# Connector.net
KiCad netlist of a schematic drawn in Altium Designer
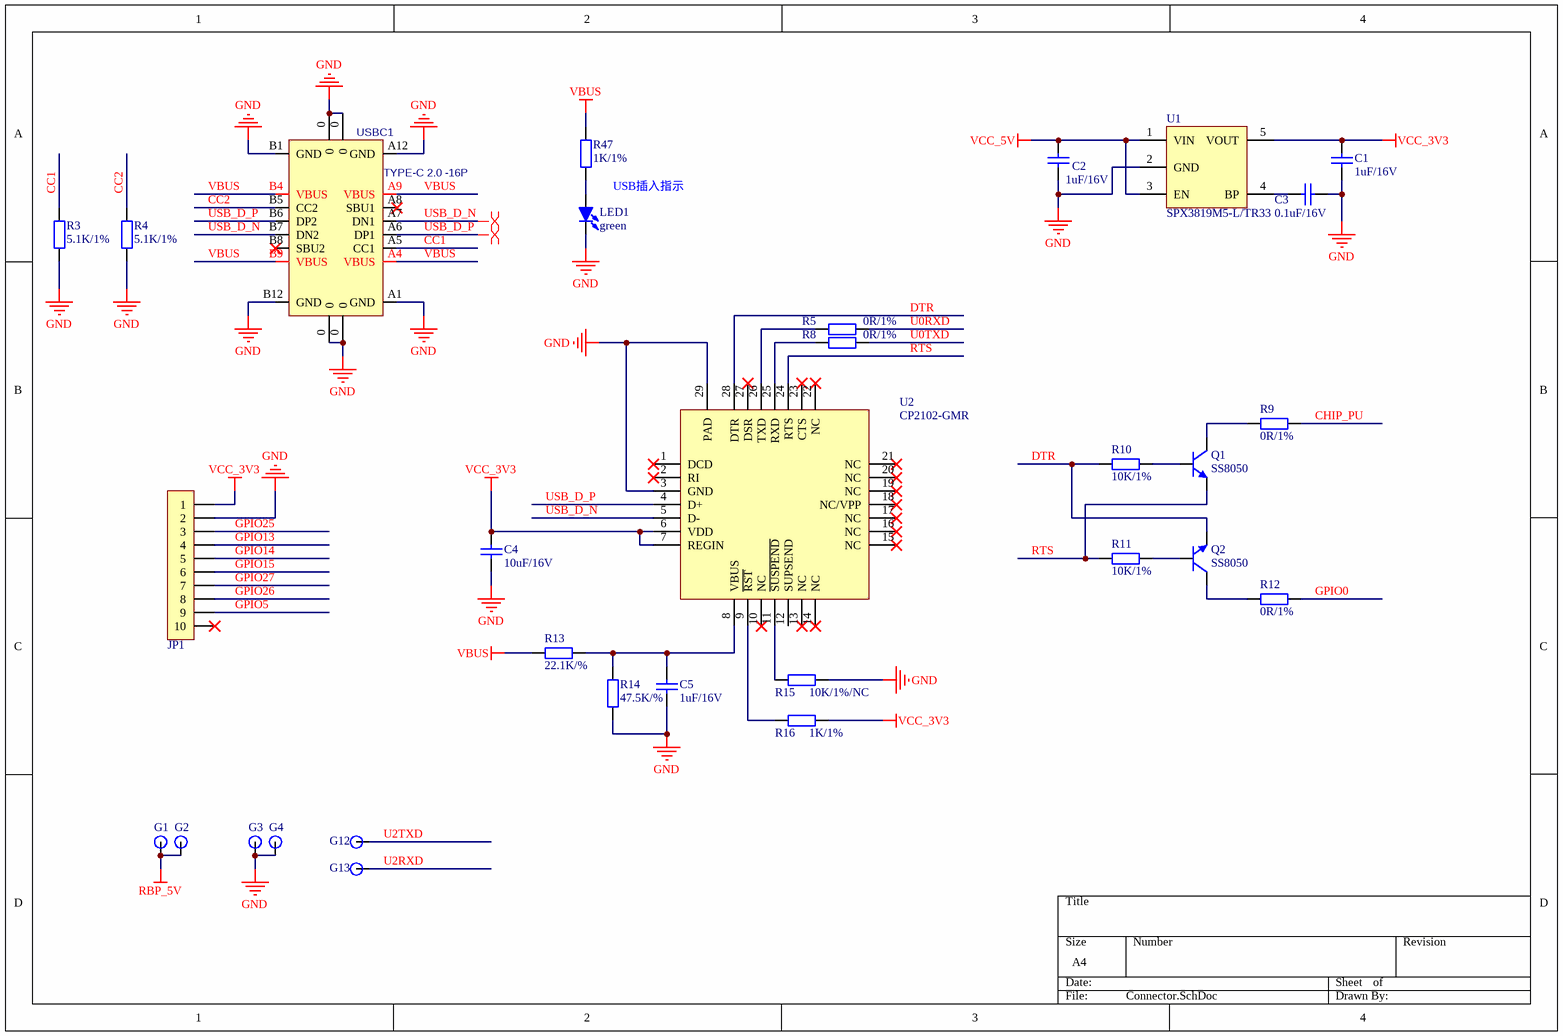
[diagram p0: Connector.SchDoc]

(export (version "E")
  (design (tool "Eeschema 10.0.6"))
  (components
    (comp (ref "C1")
      (value "1uF/16V")
      (footprint "C0402_L")
      (description "贴片电容")
      (libsource (lib "0.1 - 电阻-电容-电感-晶振-晶体-磁珠-电位器") (part "C"))
    )
    (comp (ref "C2")
      (value "1uF/16V")
      (footprint "C0402_L")
      (description "贴片电容")
      (libsource (lib "0.1 - 电阻-电容-电感-晶振-晶体-磁珠-电位器") (part "C"))
    )
    (comp (ref "C3")
      (value "0.1uF/16V")
      (footprint "C0402_L")
      (description "贴片电容")
      (libsource (lib "0.1 - 电阻-电容-电感-晶振-晶体-磁珠-电位器") (part "C"))
    )
    (comp (ref "C4")
      (value "10uF/16V")
      (footprint "C0603_L")
      (description "贴片电容")
      (libsource (lib "0.1 - 电阻-电容-电感-晶振-晶体-磁珠-电位器") (part "C"))
    )
    (comp (ref "C5")
      (value "1uF/16V")
      (footprint "C0402_L")
      (description "贴片电容")
      (libsource (lib "0.1 - 电阻-电容-电感-晶振-晶体-磁珠-电位器") (part "C"))
    )
    (comp (ref "G1") (value "RBP_GPIO") (footprint "PA100-A3") (libsource (lib "USER_Lib") (part "RBP_GPIO")))
    (comp (ref "G2") (value "RBP_GPIO") (footprint "PA100-A3") (libsource (lib "USER_Lib") (part "RBP_GPIO")))
    (comp (ref "G3") (value "RBP_GPIO") (footprint "PA100-A3") (libsource (lib "USER_Lib") (part "RBP_GPIO")))
    (comp (ref "G4") (value "RBP_GPIO") (footprint "PA100-A3") (libsource (lib "USER_Lib") (part "RBP_GPIO")))
    (comp (ref "G12")
      (value "RBP_GPIO")
      (footprint "PA100-A3")
      (libsource (lib "USER_Lib") (part "RBP_GPIO"))
    )
    (comp (ref "G13")
      (value "RBP_GPIO")
      (footprint "PA100-A3")
      (libsource (lib "USER_Lib") (part "RBP_GPIO"))
    )
    (comp (ref "JP1")
      (value "CON-10P")
      (footprint "SH1.0-WT-10P")
      (description "10P连接器")
      (libsource (lib "5.0 - 1.00mm连接器(FPC1.0-SH1.0)") (part "Header 10"))
    )
    (comp (ref "LED1")
      (value "green")
      (footprint "LED0402")
      (description "贴片LED")
      (libsource (lib "0.3 - LED发光二极管-IR二极管_接收管-光耦") (part "LED-SMD"))
    )
    (comp (ref "Q1")
      (value "SS8050")
      (footprint "SOT23-3L")
      (description "高频放大-NPN型")
      (libsource (lib "0.4 - 三极管-场效应管-可控硅") (part "8050-SMD"))
    )
    (comp (ref "Q2")
      (value "SS8050")
      (footprint "SOT23-3L")
      (description "高频放大-NPN型")
      (libsource (lib "0.4 - 三极管-场效应管-可控硅") (part "8050-SMD"))
    )
    (comp (ref "R3")
      (value "5.1K/1%")
      (footprint "R0402_L")
      (description "贴片电阻")
      (libsource (lib "0.1 - 电阻-电容-电感-晶振-晶体-磁珠-电位器") (part "R"))
    )
    (comp (ref "R4")
      (value "5.1K/1%")
      (footprint "R0402_L")
      (description "贴片电阻")
      (libsource (lib "0.1 - 电阻-电容-电感-晶振-晶体-磁珠-电位器") (part "R"))
    )
    (comp (ref "R5")
      (value "0R/1%")
      (footprint "R0402_L")
      (description "贴片电阻")
      (libsource (lib "0.1 - 电阻-电容-电感-晶振-晶体-磁珠-电位器") (part "R"))
    )
    (comp (ref "R8")
      (value "0R/1%")
      (footprint "R0402_L")
      (description "贴片电阻")
      (libsource (lib "0.1 - 电阻-电容-电感-晶振-晶体-磁珠-电位器") (part "R"))
    )
    (comp (ref "R9")
      (value "0R/1%")
      (footprint "R0402_L")
      (description "贴片电阻")
      (libsource (lib "0.1 - 电阻-电容-电感-晶振-晶体-磁珠-电位器") (part "R"))
    )
    (comp (ref "R10")
      (value "10K/1%")
      (footprint "R0402_L")
      (description "贴片电阻")
      (libsource (lib "0.1 - 电阻-电容-电感-晶振-晶体-磁珠-电位器") (part "R"))
    )
    (comp (ref "R11")
      (value "10K/1%")
      (footprint "R0402_L")
      (description "贴片电阻")
      (libsource (lib "0.1 - 电阻-电容-电感-晶振-晶体-磁珠-电位器") (part "R"))
    )
    (comp (ref "R12")
      (value "0R/1%")
      (footprint "R0402_L")
      (description "贴片电阻")
      (libsource (lib "0.1 - 电阻-电容-电感-晶振-晶体-磁珠-电位器") (part "R"))
    )
    (comp (ref "R13")
      (value "22.1K/%")
      (footprint "R0402_L")
      (description "贴片电阻")
      (libsource (lib "0.1 - 电阻-电容-电感-晶振-晶体-磁珠-电位器") (part "R"))
    )
    (comp (ref "R14")
      (value "47.5K/%")
      (footprint "R0402_L")
      (description "贴片电阻")
      (libsource (lib "0.1 - 电阻-电容-电感-晶振-晶体-磁珠-电位器") (part "R"))
    )
    (comp (ref "R15")
      (value "10K/1%/NC")
      (footprint "R0402_L")
      (description "贴片电阻")
      (libsource (lib "0.1 - 电阻-电容-电感-晶振-晶体-磁珠-电位器") (part "R"))
    )
    (comp (ref "R16")
      (value "1K/1%")
      (footprint "R0402_L")
      (description "贴片电阻")
      (libsource (lib "0.1 - 电阻-电容-电感-晶振-晶体-磁珠-电位器") (part "R"))
    )
    (comp (ref "R47")
      (value "1K/1%")
      (footprint "R0402_L")
      (description "贴片电阻")
      (libsource (lib "0.1 - 电阻-电容-电感-晶振-晶体-磁珠-电位器") (part "R"))
    )
    (comp (ref "U1")
      (value "SPX3819M5-L/TR33")
      (footprint "SOT23-5L")
      (description "500ma-LDO")
      (libsource (lib "USER_Lib") (part "SPX3819M5"))
    )
    (comp (ref "U2")
      (value "CP2102-GMR")
      (footprint "QFN28 5x5_L")
      (description "USB-TTL")
      (libsource (lib "USER_Lib") (part "CP2102-GMR"))
    )
    (comp (ref "USBC1")
      (value "TYPE-C 2.0 -16P")
      (footprint "USB-C-SMD_16P")
      (description "USB2.0_Type-C_16Pin母座")
      (libsource (lib "0.6 - 电源-以太网-音频-Type-C USB插座") (part "USB2.0_Type-C_16Pin"))
    )
  )
  (nets
    (net (code "1") (name "/CC1") (class "Default")
      (node (ref "R3") (pin "2") (pinfunction "2_2") (pintype "passive"))
      (node (ref "USBC1") (pin "A5") (pinfunction "CC1_A5") (pintype "passive"))
    )
    (net (code "2") (name "/CC2") (class "Default")
      (node (ref "R4") (pin "2") (pinfunction "2_2") (pintype "passive"))
      (node (ref "USBC1") (pin "B5") (pinfunction "CC2_B5") (pintype "passive"))
    )
    (net (code "3") (name "/CHIP_PU") (class "Default")
      (node (ref "R9") (pin "2") (pinfunction "2_2") (pintype "passive"))
    )
    (net (code "4") (name "/DTR") (class "Default")
      (node (ref "Q2") (pin "2") (pinfunction "E_2") (pintype "passive"))
      (node (ref "R10") (pin "1") (pinfunction "1_1") (pintype "passive"))
      (node (ref "U2") (pin "28") (pinfunction "DTR_28") (pintype "passive"))
    )
    (net (code "5") (name "/GPIO0") (class "Default")
      (node (ref "R12") (pin "2") (pinfunction "2_2") (pintype "passive"))
    )
    (net (code "6") (name "/GPIO5") (class "Default")
      (node (ref "JP1") (pin "9") (pinfunction "9_9") (pintype "passive"))
    )
    (net (code "7") (name "/GPIO13") (class "Default")
      (node (ref "JP1") (pin "4") (pinfunction "4_4") (pintype "passive"))
    )
    (net (code "8") (name "/GPIO14") (class "Default")
      (node (ref "JP1") (pin "5") (pinfunction "5_5") (pintype "passive"))
    )
    (net (code "9") (name "/GPIO15") (class "Default")
      (node (ref "JP1") (pin "6") (pinfunction "6_6") (pintype "passive"))
    )
    (net (code "10") (name "/GPIO25") (class "Default")
      (node (ref "JP1") (pin "3") (pinfunction "3_3") (pintype "passive"))
    )
    (net (code "11") (name "/GPIO26") (class "Default")
      (node (ref "JP1") (pin "8") (pinfunction "8_8") (pintype "passive"))
    )
    (net (code "12") (name "/GPIO27") (class "Default")
      (node (ref "JP1") (pin "7") (pinfunction "7_7") (pintype "passive"))
    )
    (net (code "13") (name "/RTS") (class "Default")
      (node (ref "Q1") (pin "2") (pinfunction "E_2") (pintype "passive"))
      (node (ref "R11") (pin "1") (pinfunction "1_1") (pintype "passive"))
      (node (ref "U2") (pin "24") (pinfunction "RTS_24") (pintype "passive"))
    )
    (net (code "14") (name "/U0RXD") (class "Default")
      (node (ref "R5") (pin "2") (pinfunction "2_2") (pintype "passive"))
    )
    (net (code "15") (name "/U0TXD") (class "Default")
      (node (ref "R8") (pin "2") (pinfunction "2_2") (pintype "passive"))
    )
    (net (code "16") (name "/U2RXD") (class "Default")
      (node (ref "G13") (pin "1") (pinfunction "1_1") (pintype "passive"))
    )
    (net (code "17") (name "/U2TXD") (class "Default")
      (node (ref "G12") (pin "1") (pinfunction "1_1") (pintype "passive"))
    )
    (net (code "18") (name "/USB_D_N") (class "Default")
      (node (ref "U2") (pin "5") (pinfunction "D-_5") (pintype "passive"))
      (node (ref "USBC1") (pin "A7") (pinfunction "DN1_A7") (pintype "passive"))
      (node (ref "USBC1") (pin "B7") (pinfunction "DN2_B7") (pintype "passive"))
    )
    (net (code "19") (name "/USB_D_P") (class "Default")
      (node (ref "U2") (pin "4") (pinfunction "D+_4") (pintype "passive"))
      (node (ref "USBC1") (pin "A6") (pinfunction "DP1_A6") (pintype "passive"))
      (node (ref "USBC1") (pin "B6") (pinfunction "DP2_B6") (pintype "passive"))
    )
    (net (code "20") (name "GND") (class "Default")
      (node (ref "C1") (pin "2") (pinfunction "2_2") (pintype "passive"))
      (node (ref "C2") (pin "1") (pinfunction "1_1") (pintype "passive"))
      (node (ref "C3") (pin "2") (pinfunction "2_2") (pintype "passive"))
      (node (ref "C4") (pin "1") (pinfunction "1_1") (pintype "passive"))
      (node (ref "C5") (pin "1") (pinfunction "1_1") (pintype "passive"))
      (node (ref "G3") (pin "1") (pinfunction "1_1") (pintype "passive"))
      (node (ref "G4") (pin "1") (pinfunction "1_1") (pintype "passive"))
      (node (ref "JP1") (pin "2") (pinfunction "2_2") (pintype "passive"))
      (node (ref "LED1") (pin "2") (pinfunction "K_2") (pintype "passive"))
      (node (ref "R14") (pin "1") (pinfunction "1_1") (pintype "passive"))
      (node (ref "R15") (pin "2") (pinfunction "2_2") (pintype "passive"))
      (node (ref "R3") (pin "1") (pinfunction "1_1") (pintype "passive"))
      (node (ref "R4") (pin "1") (pinfunction "1_1") (pintype "passive"))
      (node (ref "U1") (pin "2") (pinfunction "GND_2") (pintype "passive"))
      (node (ref "U2") (pin "29") (pinfunction "PAD_29") (pintype "passive"))
      (node (ref "U2") (pin "3") (pinfunction "GND_3") (pintype "passive"))
      (node (ref "USBC1") (pin "0") (pinfunction "0_0") (pintype "passive"))
      (node (ref "USBC1") (pin "A1") (pinfunction "GND_A1") (pintype "passive"))
      (node (ref "USBC1") (pin "A12") (pinfunction "GND_A12") (pintype "passive"))
      (node (ref "USBC1") (pin "B1") (pinfunction "GND_B1") (pintype "passive"))
      (node (ref "USBC1") (pin "B12") (pinfunction "GND_B12") (pintype "passive"))
    )
    (net (code "21") (name "Net-(LED1-A)") (class "Default")
      (node (ref "LED1") (pin "1") (pinfunction "A_1") (pintype "passive"))
      (node (ref "R47") (pin "2") (pinfunction "2_2") (pintype "passive"))
    )
    (net (code "22") (name "Net-(Q1-B)") (class "Default")
      (node (ref "Q1") (pin "1") (pinfunction "B_1") (pintype "passive"))
      (node (ref "R10") (pin "2") (pinfunction "2_2") (pintype "passive"))
    )
    (net (code "23") (name "Net-(Q1-C)") (class "Default")
      (node (ref "Q1") (pin "3") (pinfunction "C_3") (pintype "passive"))
      (node (ref "R9") (pin "1") (pinfunction "1_1") (pintype "passive"))
    )
    (net (code "24") (name "Net-(Q2-B)") (class "Default")
      (node (ref "Q2") (pin "1") (pinfunction "B_1") (pintype "passive"))
      (node (ref "R11") (pin "2") (pinfunction "2_2") (pintype "passive"))
    )
    (net (code "25") (name "Net-(Q2-C)") (class "Default")
      (node (ref "Q2") (pin "3") (pinfunction "C_3") (pintype "passive"))
      (node (ref "R12") (pin "1") (pinfunction "1_1") (pintype "passive"))
    )
    (net (code "26") (name "Net-(U1-BP)") (class "Default")
      (node (ref "C3") (pin "1") (pinfunction "1_1") (pintype "passive"))
      (node (ref "U1") (pin "4") (pinfunction "BP_4") (pintype "passive"))
    )
    (net (code "27") (name "Net-(U2-RXD)") (class "Default")
      (node (ref "R8") (pin "1") (pinfunction "1_1") (pintype "passive"))
      (node (ref "U2") (pin "25") (pinfunction "RXD_25") (pintype "passive"))
    )
    (net (code "28") (name "Net-(U2-TXD)") (class "Default")
      (node (ref "R5") (pin "1") (pinfunction "1_1") (pintype "passive"))
      (node (ref "U2") (pin "26") (pinfunction "TXD_26") (pintype "passive"))
    )
    (net (code "29") (name "Net-(U2-VBUS)") (class "Default")
      (node (ref "C5") (pin "2") (pinfunction "2_2") (pintype "passive"))
      (node (ref "R13") (pin "2") (pinfunction "2_2") (pintype "passive"))
      (node (ref "R14") (pin "2") (pinfunction "2_2") (pintype "passive"))
      (node (ref "U2") (pin "8") (pinfunction "VBUS_8") (pintype "passive"))
    )
    (net (code "30") (name "Net-(U2-~{RST})") (class "Default")
      (node (ref "R16") (pin "1") (pinfunction "1_1") (pintype "passive"))
      (node (ref "U2") (pin "9") (pinfunction "~{RST}_9") (pintype "passive"))
    )
    (net (code "31") (name "Net-(U2-~{SUSPEND})") (class "Default")
      (node (ref "R15") (pin "1") (pinfunction "1_1") (pintype "passive"))
      (node (ref "U2") (pin "11") (pinfunction "~{SUSPEND}_11") (pintype "passive"))
    )
    (net (code "32") (name "RBP_5V") (class "Default")
      (node (ref "G1") (pin "1") (pinfunction "1_1") (pintype "passive"))
      (node (ref "G2") (pin "1") (pinfunction "1_1") (pintype "passive"))
    )
    (net (code "33") (name "VBUS") (class "Default")
      (node (ref "R13") (pin "1") (pinfunction "1_1") (pintype "passive"))
      (node (ref "R47") (pin "1") (pinfunction "1_1") (pintype "passive"))
      (node (ref "USBC1") (pin "A4") (pinfunction "VBUS_A4") (pintype "passive"))
      (node (ref "USBC1") (pin "A9") (pinfunction "VBUS_A9") (pintype "passive"))
      (node (ref "USBC1") (pin "B4") (pinfunction "VBUS_B4") (pintype "passive"))
      (node (ref "USBC1") (pin "B9") (pinfunction "VBUS_B9") (pintype "passive"))
    )
    (net (code "34") (name "VCC_3V3") (class "Default")
      (node (ref "C1") (pin "1") (pinfunction "1_1") (pintype "passive"))
      (node (ref "C4") (pin "2") (pinfunction "2_2") (pintype "passive"))
      (node (ref "JP1") (pin "1") (pinfunction "1_1") (pintype "passive"))
      (node (ref "R16") (pin "2") (pinfunction "2_2") (pintype "passive"))
      (node (ref "U1") (pin "5") (pinfunction "VOUT_5") (pintype "passive"))
      (node (ref "U2") (pin "6") (pinfunction "VDD_6") (pintype "passive"))
      (node (ref "U2") (pin "7") (pinfunction "REGIN_7") (pintype "passive"))
    )
    (net (code "35") (name "VCC_5V") (class "Default")
      (node (ref "C2") (pin "2") (pinfunction "2_2") (pintype "passive"))
      (node (ref "U1") (pin "1") (pinfunction "VIN_1") (pintype "passive"))
      (node (ref "U1") (pin "3") (pinfunction "EN_3") (pintype "passive"))
    )
    (net (code "36") (name "unconnected-(JP1-Pad10)") (class "Default")
      (node (ref "JP1") (pin "10") (pinfunction "10_10") (pintype "passive+no_connect"))
    )
    (net (code "37") (name "unconnected-(U2-CTS-Pad23)") (class "Default")
      (node (ref "U2") (pin "23") (pinfunction "CTS_23") (pintype "passive+no_connect"))
    )
    (net (code "38") (name "unconnected-(U2-DCD-Pad1)") (class "Default")
      (node (ref "U2") (pin "1") (pinfunction "DCD_1") (pintype "passive+no_connect"))
    )
    (net (code "39") (name "unconnected-(U2-DSR-Pad27)") (class "Default")
      (node (ref "U2") (pin "27") (pinfunction "DSR_27") (pintype "passive+no_connect"))
    )
    (net (code "40") (name "unconnected-(U2-NC-Pad10)") (class "Default")
      (node (ref "U2") (pin "10") (pinfunction "NC_10") (pintype "passive+no_connect"))
    )
    (net (code "41") (name "unconnected-(U2-NC-Pad13)") (class "Default")
      (node (ref "U2") (pin "13") (pinfunction "NC_13") (pintype "passive+no_connect"))
    )
    (net (code "42") (name "unconnected-(U2-NC-Pad14)") (class "Default")
      (node (ref "U2") (pin "14") (pinfunction "NC_14") (pintype "passive+no_connect"))
    )
    (net (code "43") (name "unconnected-(U2-NC-Pad15)") (class "Default")
      (node (ref "U2") (pin "15") (pinfunction "NC_15") (pintype "passive+no_connect"))
    )
    (net (code "44") (name "unconnected-(U2-NC-Pad16)") (class "Default")
      (node (ref "U2") (pin "16") (pinfunction "NC_16") (pintype "passive+no_connect"))
    )
    (net (code "45") (name "unconnected-(U2-NC-Pad17)") (class "Default")
      (node (ref "U2") (pin "17") (pinfunction "NC_17") (pintype "passive+no_connect"))
    )
    (net (code "46") (name "unconnected-(U2-NC-Pad19)") (class "Default")
      (node (ref "U2") (pin "19") (pinfunction "NC_19") (pintype "passive+no_connect"))
    )
    (net (code "47") (name "unconnected-(U2-NC-Pad20)") (class "Default")
      (node (ref "U2") (pin "20") (pinfunction "NC_20") (pintype "passive+no_connect"))
    )
    (net (code "48") (name "unconnected-(U2-NC-Pad21)") (class "Default")
      (node (ref "U2") (pin "21") (pinfunction "NC_21") (pintype "passive+no_connect"))
    )
    (net (code "49") (name "unconnected-(U2-NC-Pad22)") (class "Default")
      (node (ref "U2") (pin "22") (pinfunction "NC_22") (pintype "passive+no_connect"))
    )
    (net (code "50") (name "unconnected-(U2-NC{slash}VPP-Pad18)") (class "Default")
      (node (ref "U2") (pin "18") (pinfunction "NC/VPP_18") (pintype "passive+no_connect"))
    )
    (net (code "51") (name "unconnected-(U2-RI-Pad2)") (class "Default")
      (node (ref "U2") (pin "2") (pinfunction "RI_2") (pintype "passive+no_connect"))
    )
    (net (code "52") (name "unconnected-(U2-SUPSEND-Pad12)") (class "Default")
      (node (ref "U2") (pin "12") (pinfunction "SUPSEND_12") (pintype "passive"))
    )
    (net (code "53") (name "unconnected-(USBC1-SBU1-PadA8)") (class "Default")
      (node (ref "USBC1") (pin "A8") (pinfunction "SBU1_A8") (pintype "passive+no_connect"))
    )
    (net (code "54") (name "unconnected-(USBC1-SBU2-PadB8)") (class "Default")
      (node (ref "USBC1") (pin "B8") (pinfunction "SBU2_B8") (pintype "passive+no_connect"))
    )
  )
)
